# Audio.net
KiCad netlist of a schematic drawn in Altium Designer
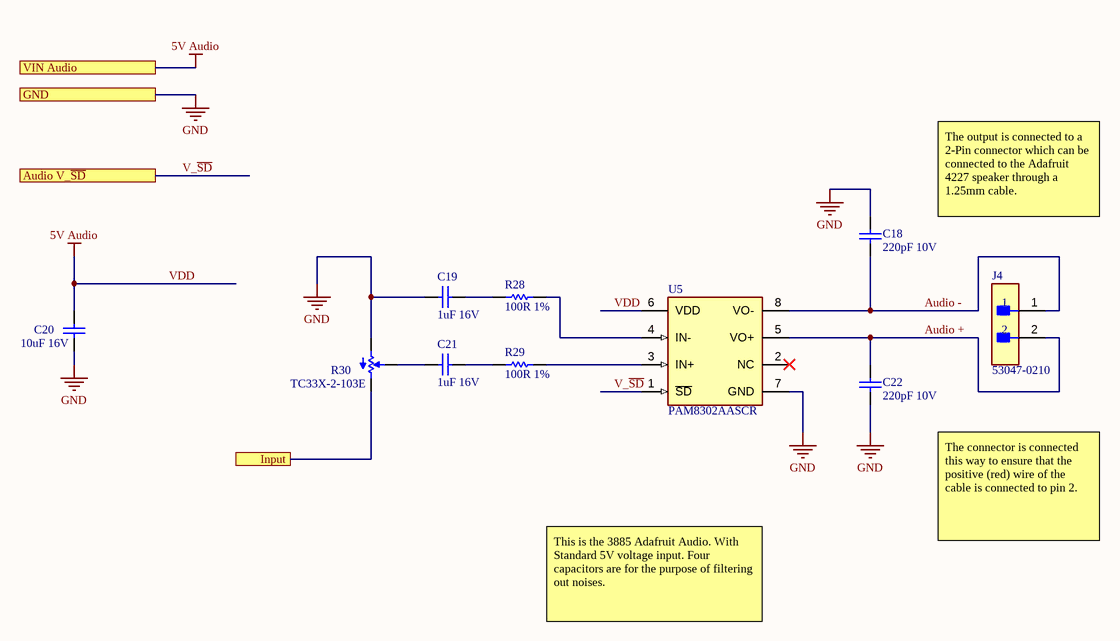
[diagram p0: Audio.SchDoc]

(export (version "E")
  (design (tool "Eeschema 10.0.6"))
  (components
    (comp (ref "C18")
      (value "220pF 10V")
      (footprint "CAPC0603(1608)100_N")
      (description "CAP 220pF 10V ±2% 0603 (1608 Metric) Thickness 1mm SMD")
      (fields (field (name "TOLERANCE") "Â±2%"))
      (libsource (lib "Altium Content Vault") (part "CAP"))
    )
    (comp (ref "C19")
      (value "1uF 16V")
      (footprint "CAPC0603(1608)100_N")
      (description "CAP 1uF 16V ±5% 0603 (1608 Metric) Thickness 1mm SMD")
      (fields (field (name "TOLERANCE") "Â±5%"))
      (libsource (lib "Altium Content Vault") (part "CAP"))
    )
    (comp (ref "C20")
      (value "10uF 16V")
      (footprint "CAPC0805(2012)145_L")
      (description "CAP 10uF 16V ±10% 0805 (2012 Metric) Thickness 1.45mm SMD")
      (fields (field (name "TOLERANCE") "Â±10%"))
      (libsource (lib "Altium Content Vault") (part "CAP"))
    )
    (comp (ref "C21")
      (value "1uF 16V")
      (footprint "CAPC0603(1608)100_N")
      (description "CAP 1uF 16V ±5% 0603 (1608 Metric) Thickness 1mm SMD")
      (fields (field (name "TOLERANCE") "Â±5%"))
      (libsource (lib "Altium Content Vault") (part "CAP"))
    )
    (comp (ref "C22")
      (value "220pF 10V")
      (footprint "CAPC0603(1608)100_N")
      (description "CAP 220pF 10V ±2% 0603 (1608 Metric) Thickness 1mm SMD")
      (fields (field (name "TOLERANCE") "Â±2%"))
      (libsource (lib "Altium Content Vault") (part "CAP"))
    )
    (comp (ref "J4")
      (value "53047-0210")
      (footprint "FP-53047-0210-MFG")
      (description "CONN HEADER VERT 2POS 1.25MM")
      (fields
        (field (name "OCTOPART") "https://octopart.com/53047-0210-molex-276772")
        (field (name "MANUFACTURER") "Molex")
      )
      (libsource (lib "audio") (part "CMP-2000-05628-3"))
    )
    (comp (ref "R28")
      (value "100R 1%")
      (footprint "RESC0603(1608)_M")
      (description "100R 0.1W 1% 0603 (1608 Metric)  SMD")
      (fields (field (name "TOLERANCE") "1 %") (field (name "POWER") "0.1 W"))
      (libsource (lib "Altium Content Vault") (part "RES"))
    )
    (comp (ref "R29")
      (value "100R 1%")
      (footprint "RESC0603(1608)_M")
      (description "100R 0.1W 1% 0603 (1608 Metric)  SMD")
      (fields (field (name "TOLERANCE") "1 %") (field (name "POWER") "0.1 W"))
      (libsource (lib "Altium Content Vault") (part "RES"))
    )
    (comp (ref "R30")
      (value "TC33X-2-103E")
      (footprint "BOUR-TC33X-2_V")
      (description "Trimming Potentiometer, 10000 Ohm, -40 to 100 degC, 3-Pin SMD, RoHS, Tape and Reel")
      (fields (field (name "TOLERANCE") "25%") (field (name "MANUFACTURER") "Bourns"))
      (libsource (lib "audio") (part "CMP-2100-03695-1"))
    )
    (comp (ref "U5")
      (value "PAM8302AASCR")
      (footprint "FP-MSOP-8-MFG")
      (description "IC AMP CLASS D MONO 2.5W 8MSOP")
      (fields
        (field (name "MANUFACTURER") "Diodes Inc.")
        (field (name "OCTOPART") "https://octopart.com/pam8302aascr-diodes+inc.-29030473")
      )
      (libsource (lib "audio") (part "CMP-12733-000002-1"))
    )
  )
  (nets
    (net (code "1") (name "/Audio +") (class "Default")
      (node (ref "C22") (pin "2") (pinfunction "2_2") (pintype "passive"))
      (node (ref "J4") (pin "2") (pinfunction "2_2") (pintype "passive"))
      (node (ref "U5") (pin "5") (pinfunction "VO+_5") (pintype "power_in"))
    )
    (net (code "2") (name "/Audio -") (class "Default")
      (node (ref "C18") (pin "2") (pinfunction "2_2") (pintype "passive"))
      (node (ref "J4") (pin "1") (pinfunction "1_1") (pintype "passive"))
      (node (ref "U5") (pin "8") (pinfunction "VO-_8") (pintype "power_in"))
    )
    (net (code "3") (name "/Input") (class "Default")
      (node (ref "R30") (pin "1") (pinfunction "1_1") (pintype "passive"))
    )
    (net (code "4") (name "/V_~{SD}") (class "Default")
      (node (ref "U5") (pin "1") (pinfunction "~{SD}_1") (pintype "input"))
    )
    (net (code "5") (name "5V Audio") (class "Default")
      (node (ref "C20") (pin "2") (pinfunction "2_2") (pintype "passive"))
      (node (ref "U5") (pin "6") (pinfunction "VDD_6") (pintype "power_in"))
    )
    (net (code "6") (name "GND") (class "Default")
      (node (ref "C18") (pin "1") (pinfunction "1_1") (pintype "passive"))
      (node (ref "C19") (pin "2") (pinfunction "2_2") (pintype "passive"))
      (node (ref "C20") (pin "1") (pinfunction "1_1") (pintype "passive"))
      (node (ref "C22") (pin "1") (pinfunction "1_1") (pintype "passive"))
      (node (ref "R30") (pin "3") (pinfunction "3_3") (pintype "passive"))
      (node (ref "U5") (pin "7") (pinfunction "GND_7") (pintype "power_in"))
    )
    (net (code "7") (name "Net-(C19-Pad1)") (class "Default")
      (node (ref "C19") (pin "1") (pinfunction "1_1") (pintype "passive"))
      (node (ref "R28") (pin "1") (pinfunction "1_1") (pintype "passive"))
    )
    (net (code "8") (name "Net-(C21-Pad1)") (class "Default")
      (node (ref "C21") (pin "1") (pinfunction "1_1") (pintype "passive"))
      (node (ref "R29") (pin "1") (pinfunction "1_1") (pintype "passive"))
    )
    (net (code "9") (name "Net-(C21-Pad2)") (class "Default")
      (node (ref "C21") (pin "2") (pinfunction "2_2") (pintype "passive"))
      (node (ref "R30") (pin "2") (pinfunction "2_2") (pintype "passive"))
    )
    (net (code "10") (name "Net-(U5-IN+)") (class "Default")
      (node (ref "R29") (pin "2") (pinfunction "2_2") (pintype "passive"))
      (node (ref "U5") (pin "3") (pinfunction "IN+_3") (pintype "input"))
    )
    (net (code "11") (name "Net-(U5-IN-)") (class "Default")
      (node (ref "R28") (pin "2") (pinfunction "2_2") (pintype "passive"))
      (node (ref "U5") (pin "4") (pinfunction "IN-_4") (pintype "input"))
    )
    (net (code "12") (name "unconnected-(U5-NC-Pad2)") (class "Default")
      (node (ref "U5") (pin "2") (pinfunction "NC_2") (pintype "passive+no_connect"))
    )
  )
)
